# microSD.net
KiCad netlist of a schematic drawn in Altium Designer
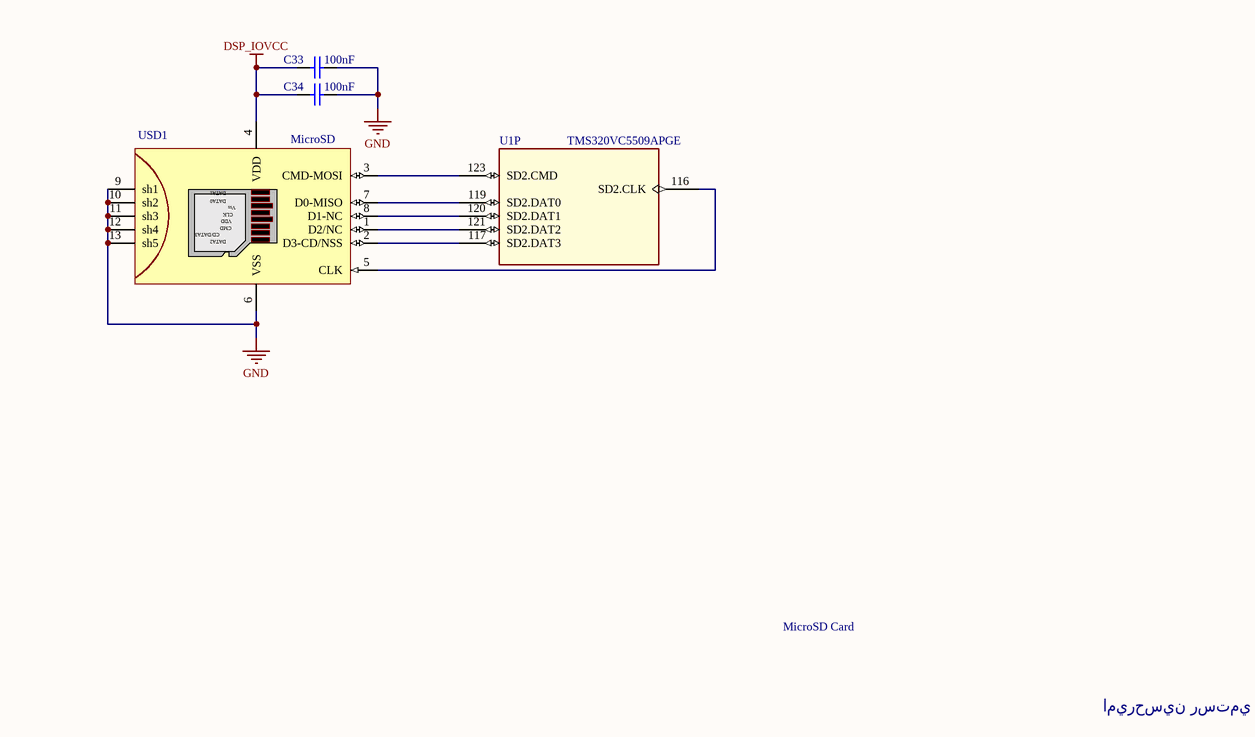
[diagram p0: microSD.SchDoc]

(export (version "E")
  (design (tool "Eeschema 10.0.6"))
  (components
    (comp (ref "C33")
      (value "100nF")
      (footprint "1608[0603]")
      (description "Capacitor")
      (fields (field (name "PUBLISHER") "Altium Limited"))
      (libsource (lib "Miscellaneous Devices") (part "Cap Semi"))
    )
    (comp (ref "C34")
      (value "100nF")
      (footprint "1608[0603]")
      (description "Capacitor")
      (fields (field (name "PUBLISHER") "Altium Limited"))
      (libsource (lib "Miscellaneous Devices") (part "Cap Semi"))
    )
    (comp (ref "U1")
      (value "TMS320VC5509APGE")
      (footprint "TMSVC5509APGA")
      (libsource (lib "TMSVC5509APGE") (part "TMS320VC5509APGE"))
    )
    (comp (ref "USD1")
      (value "MicroSD")
      (footprint "SD_MMC_SOCKET")
      (libsource (lib "MicroSD") (part "MicroSD"))
    )
  )
  (nets
    (net (code "1") (name "DSP_IOVCC") (class "Default")
      (node (ref "C33") (pin "2") (pinfunction "2_2") (pintype "passive"))
      (node (ref "C34") (pin "2") (pinfunction "2_2") (pintype "passive"))
      (node (ref "USD1") (pin "4") (pinfunction "VDD_4") (pintype "power_in"))
    )
    (net (code "2") (name "GND") (class "Default")
      (node (ref "C33") (pin "1") (pinfunction "1_1") (pintype "passive"))
      (node (ref "C34") (pin "1") (pinfunction "1_1") (pintype "passive"))
      (node (ref "USD1") (pin "10") (pinfunction "sh2_10") (pintype "passive"))
      (node (ref "USD1") (pin "11") (pinfunction "sh3_11") (pintype "passive"))
      (node (ref "USD1") (pin "12") (pinfunction "sh4_12") (pintype "passive"))
      (node (ref "USD1") (pin "13") (pinfunction "sh5_13") (pintype "passive"))
      (node (ref "USD1") (pin "6") (pinfunction "VSS_6") (pintype "power_in"))
      (node (ref "USD1") (pin "9") (pinfunction "sh1_9") (pintype "passive"))
    )
    (net (code "3") (name "Net-(U1P-SD2.CLK)") (class "Default")
      (node (ref "U1") (pin "116") (pinfunction "SD2.CLK_116") (pintype "output"))
      (node (ref "USD1") (pin "5") (pinfunction "CLK_5") (pintype "input"))
    )
    (net (code "4") (name "Net-(U1P-SD2.CMD)") (class "Default")
      (node (ref "U1") (pin "123") (pinfunction "SD2.CMD_123") (pintype "bidirectional"))
      (node (ref "USD1") (pin "3") (pinfunction "CMD-MOSI_3") (pintype "bidirectional"))
    )
    (net (code "5") (name "Net-(U1P-SD2.DAT0)") (class "Default")
      (node (ref "U1") (pin "119") (pinfunction "SD2.DAT0_119") (pintype "bidirectional"))
      (node (ref "USD1") (pin "7") (pinfunction "D0-MISO_7") (pintype "bidirectional"))
    )
    (net (code "6") (name "Net-(U1P-SD2.DAT1)") (class "Default")
      (node (ref "U1") (pin "120") (pinfunction "SD2.DAT1_120") (pintype "bidirectional"))
      (node (ref "USD1") (pin "8") (pinfunction "D1-NC_8") (pintype "bidirectional"))
    )
    (net (code "7") (name "Net-(U1P-SD2.DAT2)") (class "Default")
      (node (ref "U1") (pin "121") (pinfunction "SD2.DAT2_121") (pintype "bidirectional"))
      (node (ref "USD1") (pin "1") (pinfunction "D2/NC_1") (pintype "bidirectional"))
    )
    (net (code "8") (name "Net-(U1P-SD2.DAT3)") (class "Default")
      (node (ref "U1") (pin "117") (pinfunction "SD2.DAT3_117") (pintype "bidirectional"))
      (node (ref "USD1") (pin "2") (pinfunction "D3-CD/NSS_2") (pintype "bidirectional"))
    )
  )
)
